# UWBSubsystem.net
KiCad netlist of a schematic drawn in Altium Designer
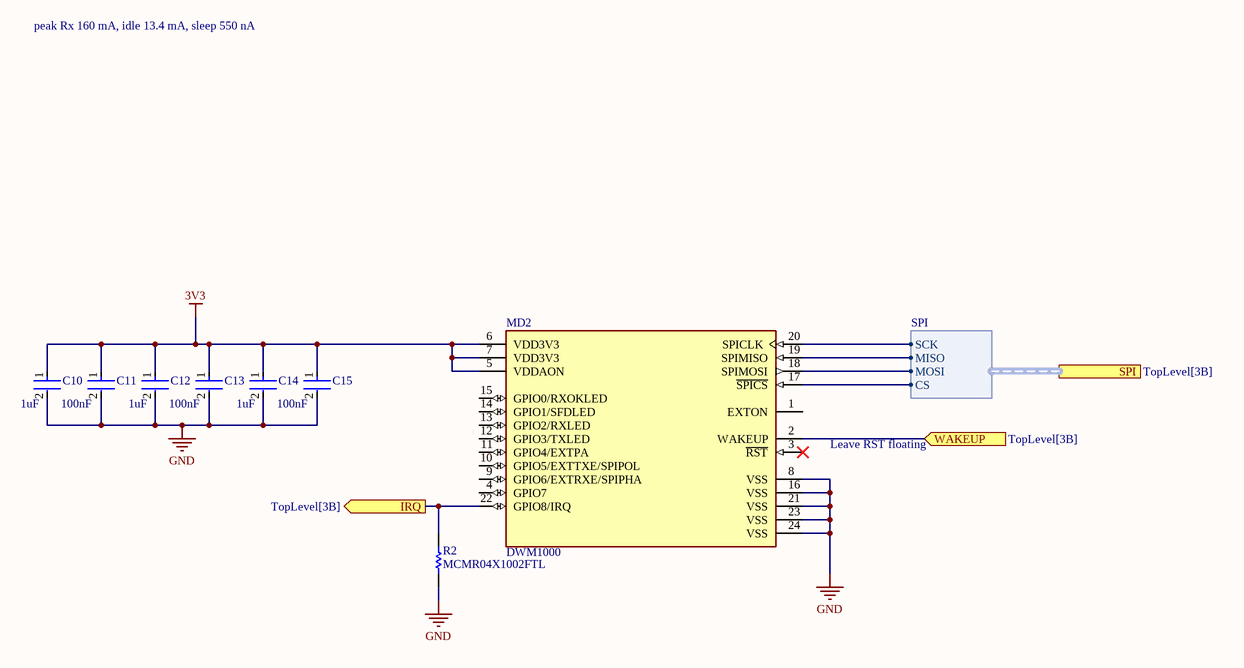
[diagram p0: UWBSubsystem.SchDoc]

(export (version "E")
  (design (tool "Eeschema 10.0.6"))
  (components
    (comp (ref "C10")
      (value "CL05A105KP5NNNC")
      (footprint "FP-CL511-IPC_C")
      (description "Cap Ceramic 1uF 10V X5R ±10% SMD 0402 +85°C Paper T/R")
      (fields (field (name "CAPACITANCE") "1uF") (field (name "TOLERANCE") "10%"))
      (libsource (lib "Altium Content Vault") (part "b4654b650e69147ec39a6b967a45e02"))
    )
    (comp (ref "C11")
      (value "GRM155R71E104KE14J")
      (footprint "FP-GRM155-0_05-IPC_C")
      (description "Chip Multilayer Ceramic Capacitors for General Purpose, 0402, 0.10uF, X7R, 15%, 10%, 25V")
      (fields (field (name "CAPACITANCE") "100nF") (field (name "TOLERANCE") "10%"))
      (libsource (lib "Altium Content Vault") (part "02cd4be3c70576c341d710602a673aa"))
    )
    (comp (ref "C12")
      (value "CL05A105KP5NNNC")
      (footprint "FP-CL511-IPC_C")
      (description "Cap Ceramic 1uF 10V X5R ±10% SMD 0402 +85°C Paper T/R")
      (fields (field (name "CAPACITANCE") "1uF") (field (name "TOLERANCE") "10%"))
      (libsource (lib "Altium Content Vault") (part "b4654b650e69147ec39a6b967a45e02"))
    )
    (comp (ref "C13")
      (value "GRM155R71E104KE14J")
      (footprint "FP-GRM155-0_05-IPC_C")
      (description "Chip Multilayer Ceramic Capacitors for General Purpose, 0402, 0.10uF, X7R, 15%, 10%, 25V")
      (fields (field (name "CAPACITANCE") "100nF") (field (name "TOLERANCE") "10%"))
      (libsource (lib "Altium Content Vault") (part "02cd4be3c70576c341d710602a673aa"))
    )
    (comp (ref "C14")
      (value "CL05A105KP5NNNC")
      (footprint "FP-CL511-IPC_C")
      (description "Cap Ceramic 1uF 10V X5R ±10% SMD 0402 +85°C Paper T/R")
      (fields (field (name "CAPACITANCE") "1uF") (field (name "TOLERANCE") "10%"))
      (libsource (lib "Altium Content Vault") (part "b4654b650e69147ec39a6b967a45e02"))
    )
    (comp (ref "C15")
      (value "GRM155R71E104KE14J")
      (footprint "FP-GRM155-0_05-IPC_C")
      (description "Chip Multilayer Ceramic Capacitors for General Purpose, 0402, 0.10uF, X7R, 15%, 10%, 25V")
      (fields (field (name "CAPACITANCE") "100nF") (field (name "TOLERANCE") "10%"))
      (libsource (lib "Altium Content Vault") (part "02cd4be3c70576c341d710602a673aa"))
    )
    (comp (ref "MD2")
      (value "DWM1000")
      (footprint "FP-DWM1000-MFG")
      (description "RX TXRX MODULE 802.15.4 CHIP SMD")
      (libsource (lib "Altium Content Vault") (part "f696d20320cfac42d99354fdc9dc59a"))
    )
    (comp (ref "R2")
      (value "MCMR04X1002FTL")
      (footprint "RESC1005X40X25NL05T10")
      (fields (field (name "MANUFACTURER") "Multicomp"))
      (libsource (lib "Altium Content Vault") (part "RES"))
    )
  )
  (nets
    (net (code "2") (name "/CS") (class "Default")
      (node (ref "MD2") (pin "17") (pinfunction "~{SPICS}_17") (pintype "input"))
    )
    (net (code "3") (name "/IRQ") (class "Default")
      (node (ref "MD2") (pin "22") (pinfunction "GPIO8/IRQ_22") (pintype "bidirectional"))
      (node (ref "R2") (pin "2") (pinfunction "2_2") (pintype "passive"))
    )
    (net (code "4") (name "/MISO") (class "Default")
      (node (ref "MD2") (pin "19") (pinfunction "SPIMISO_19") (pintype "input"))
    )
    (net (code "5") (name "/MOSI") (class "Default")
      (node (ref "MD2") (pin "18") (pinfunction "SPIMOSI_18") (pintype "output"))
    )
    (net (code "6") (name "/SCK") (class "Default")
      (node (ref "MD2") (pin "20") (pinfunction "SPICLK_20") (pintype "input"))
    )
    (net (code "7") (name "/WAKEUP") (class "Default")
      (node (ref "MD2") (pin "2") (pinfunction "WAKEUP_2") (pintype "passive"))
    )
    (net (code "9") (name "3V3") (class "Default")
      (node (ref "C10") (pin "1") (pinfunction "1_1") (pintype "passive"))
      (node (ref "C11") (pin "1") (pinfunction "1_1") (pintype "passive"))
      (node (ref "C12") (pin "1") (pinfunction "1_1") (pintype "passive"))
      (node (ref "C13") (pin "1") (pinfunction "1_1") (pintype "passive"))
      (node (ref "C14") (pin "1") (pinfunction "1_1") (pintype "passive"))
      (node (ref "C15") (pin "1") (pinfunction "1_1") (pintype "passive"))
      (node (ref "MD2") (pin "5") (pinfunction "VDDAON_5") (pintype "power_in"))
      (node (ref "MD2") (pin "6") (pinfunction "VDD3V3_6") (pintype "power_in"))
      (node (ref "MD2") (pin "7") (pinfunction "VDD3V3_7") (pintype "power_in"))
    )
    (net (code "10") (name "GND") (class "Default")
      (node (ref "C10") (pin "2") (pinfunction "2_2") (pintype "passive"))
      (node (ref "C11") (pin "2") (pinfunction "2_2") (pintype "passive"))
      (node (ref "C12") (pin "2") (pinfunction "2_2") (pintype "passive"))
      (node (ref "C13") (pin "2") (pinfunction "2_2") (pintype "passive"))
      (node (ref "C14") (pin "2") (pinfunction "2_2") (pintype "passive"))
      (node (ref "C15") (pin "2") (pinfunction "2_2") (pintype "passive"))
      (node (ref "MD2") (pin "16") (pinfunction "VSS_16") (pintype "power_in"))
      (node (ref "MD2") (pin "21") (pinfunction "VSS_21") (pintype "power_in"))
      (node (ref "MD2") (pin "23") (pinfunction "VSS_23") (pintype "power_in"))
      (node (ref "MD2") (pin "24") (pinfunction "VSS_24") (pintype "power_in"))
      (node (ref "MD2") (pin "8") (pinfunction "VSS_8") (pintype "power_in"))
      (node (ref "R2") (pin "1") (pinfunction "1_1") (pintype "passive"))
    )
    (net (code "11") (name "unconnected-(MD2-EXTON-Pad1)") (class "Default")
      (node (ref "MD2") (pin "1") (pinfunction "EXTON_1") (pintype "passive"))
    )
    (net (code "12") (name "unconnected-(MD2-GPIO0{slash}RXOKLED-Pad15)") (class "Default")
      (node (ref "MD2") (pin "15") (pinfunction "GPIO0/RXOKLED_15") (pintype "bidirectional"))
    )
    (net (code "13") (name "unconnected-(MD2-GPIO1{slash}SFDLED-Pad14)") (class "Default")
      (node (ref "MD2") (pin "14") (pinfunction "GPIO1/SFDLED_14") (pintype "bidirectional"))
    )
    (net (code "14") (name "unconnected-(MD2-GPIO2{slash}RXLED-Pad13)") (class "Default")
      (node (ref "MD2") (pin "13") (pinfunction "GPIO2/RXLED_13") (pintype "bidirectional"))
    )
    (net (code "15") (name "unconnected-(MD2-GPIO3{slash}TXLED-Pad12)") (class "Default")
      (node (ref "MD2") (pin "12") (pinfunction "GPIO3/TXLED_12") (pintype "bidirectional"))
    )
    (net (code "16") (name "unconnected-(MD2-GPIO4{slash}EXTPA-Pad11)") (class "Default")
      (node (ref "MD2") (pin "11") (pinfunction "GPIO4/EXTPA_11") (pintype "bidirectional"))
    )
    (net (code "17") (name "unconnected-(MD2-GPIO5{slash}EXTTXE{slash}SPIPOL-Pad10)") (class "Default")
      (node (ref "MD2") (pin "10") (pinfunction "GPIO5/EXTTXE/SPIPOL_10") (pintype "bidirectional"))
    )
    (net (code "18") (name "unconnected-(MD2-GPIO6{slash}EXTRXE{slash}SPIPHA-Pad9)") (class "Default")
      (node (ref "MD2") (pin "9") (pinfunction "GPIO6/EXTRXE/SPIPHA_9") (pintype "bidirectional"))
    )
    (net (code "19") (name "unconnected-(MD2-GPIO7-Pad4)") (class "Default")
      (node (ref "MD2") (pin "4") (pinfunction "GPIO7_4") (pintype "bidirectional"))
    )
    (net (code "20") (name "unconnected-(MD2-~{RST}-Pad3)") (class "Default")
      (node (ref "MD2") (pin "3") (pinfunction "~{RST}_3") (pintype "input+no_connect"))
    )
  )
)
